# Integration_board_3008_version_2.net
KiCad netlist of a schematic drawn in EAGLE
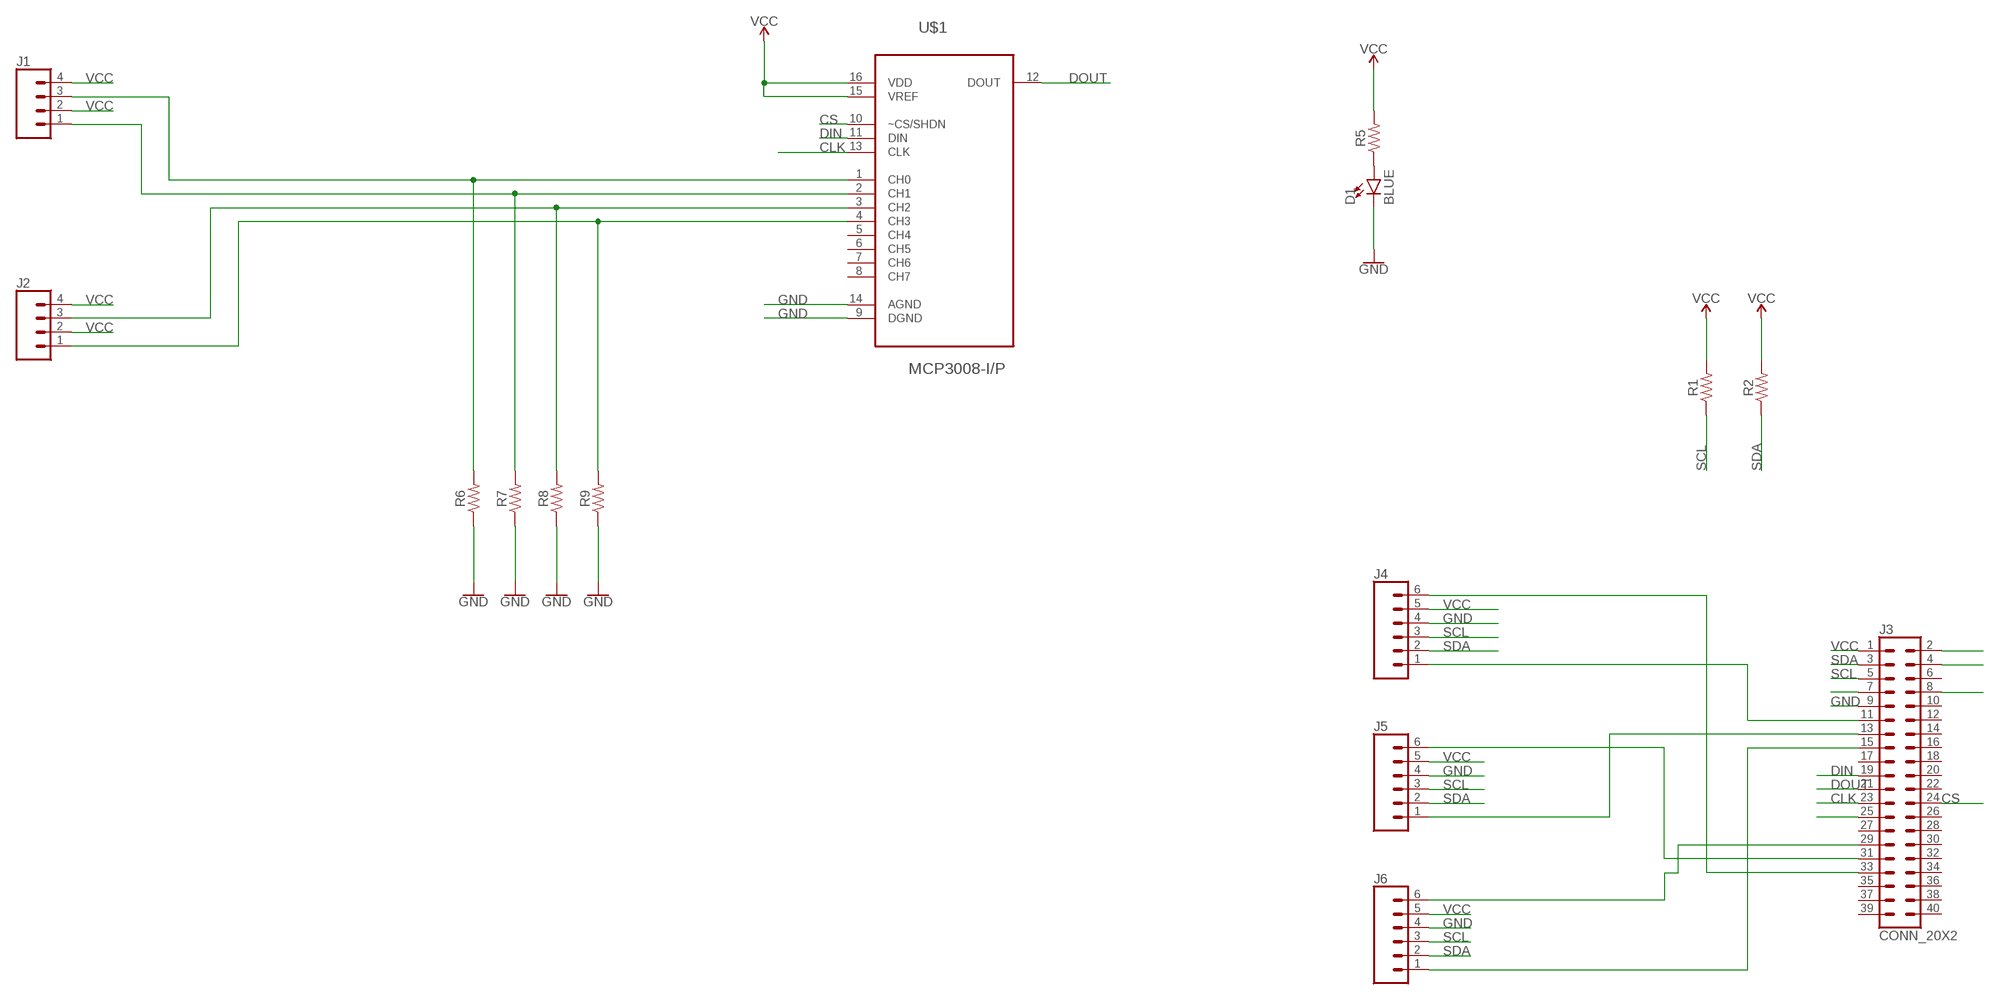
[diagram p0: schematic, sheet 1]

(export (version "E")
  (design (tool "Eeschema 10.0.6"))
  (components
    (comp (ref "D1")
      (value "BLUE")
      (footprint "eagle-import:LED-0603")
      (libsource (lib "eagle-import") (part "LED-BLUE0603"))
    )
    (comp (ref "J1")
      (value "CONN_04PTH")
      (footprint "eagle-import:1X04")
      (libsource (lib "eagle-import") (part "CONN_04PTH"))
    )
    (comp (ref "J2")
      (value "CONN_04PTH")
      (footprint "eagle-import:1X04")
      (libsource (lib "eagle-import") (part "CONN_04PTH"))
    )
    (comp (ref "J3")
      (value "CONN_20X2")
      (footprint "eagle-import:2X20")
      (libsource (lib "eagle-import") (part "CONN_20X2"))
    )
    (comp (ref "J4")
      (value "CONN_06SILK_FEMALE_PTH")
      (footprint "eagle-import:1X06")
      (libsource (lib "eagle-import") (part "CONN_06SILK_FEMALE_PTH"))
    )
    (comp (ref "J5")
      (value "CONN_06SILK_FEMALE_PTH")
      (footprint "eagle-import:1X06")
      (libsource (lib "eagle-import") (part "CONN_06SILK_FEMALE_PTH"))
    )
    (comp (ref "J6")
      (value "CONN_06SILK_FEMALE_PTH")
      (footprint "eagle-import:1X06")
      (libsource (lib "eagle-import") (part "CONN_06SILK_FEMALE_PTH"))
    )
    (comp (ref "R1")
      (value "RESISTOR0805")
      (footprint "eagle-import:0805")
      (libsource (lib "eagle-import") (part "RESISTOR0805"))
    )
    (comp (ref "R2")
      (value "RESISTOR0805")
      (footprint "eagle-import:0805")
      (libsource (lib "eagle-import") (part "RESISTOR0805"))
    )
    (comp (ref "R5")
      (value "RESISTOR0805")
      (footprint "eagle-import:0805")
      (libsource (lib "eagle-import") (part "RESISTOR0805"))
    )
    (comp (ref "R6")
      (value "RESISTOR0805")
      (footprint "eagle-import:0805")
      (libsource (lib "eagle-import") (part "RESISTOR0805"))
    )
    (comp (ref "R7")
      (value "RESISTOR0805")
      (footprint "eagle-import:0805")
      (libsource (lib "eagle-import") (part "RESISTOR0805"))
    )
    (comp (ref "R8")
      (value "RESISTOR0805")
      (footprint "eagle-import:0805")
      (libsource (lib "eagle-import") (part "RESISTOR0805"))
    )
    (comp (ref "R9")
      (value "RESISTOR0805")
      (footprint "eagle-import:0805")
      (libsource (lib "eagle-import") (part "RESISTOR0805"))
    )
    (comp (ref "U$1")
      (value "MCP3008-I/P")
      (footprint "eagle-import:DIP254P762X432-16")
      (libsource (lib "eagle-import") (part "MCP3008-I/P"))
    )
  )
  (nets
    (net (code "1") (name "/CLK") (class "Default")
      (node (ref "J3") (pin "23") (pinfunction "23_23") (pintype "passive"))
      (node (ref "U$1") (pin "13") (pinfunction "CLK_13") (pintype "input"))
    )
    (net (code "2") (name "/CS") (class "Default")
      (node (ref "J3") (pin "24") (pinfunction "24_24") (pintype "passive"))
      (node (ref "U$1") (pin "10") (pinfunction "~{CS/SHDN}_10") (pintype "input"))
    )
    (net (code "3") (name "/DIN") (class "Default")
      (node (ref "J3") (pin "19") (pinfunction "19_19") (pintype "passive"))
      (node (ref "U$1") (pin "11") (pinfunction "DIN_11") (pintype "input"))
    )
    (net (code "4") (name "/DOUT") (class "Default")
      (node (ref "J3") (pin "21") (pinfunction "21_21") (pintype "passive"))
      (node (ref "U$1") (pin "12") (pinfunction "DOUT_12") (pintype "output"))
    )
    (net (code "5") (name "/SCL") (class "Default")
      (node (ref "J3") (pin "5") (pinfunction "5_5") (pintype "passive"))
      (node (ref "J4") (pin "3") (pinfunction "3_3") (pintype "passive"))
      (node (ref "J5") (pin "3") (pinfunction "3_3") (pintype "passive"))
      (node (ref "J6") (pin "3") (pinfunction "3_3") (pintype "passive"))
      (node (ref "R1") (pin "1") (pinfunction "1_1") (pintype "passive"))
    )
    (net (code "6") (name "/SDA") (class "Default")
      (node (ref "J3") (pin "3") (pinfunction "3_3") (pintype "passive"))
      (node (ref "J4") (pin "2") (pinfunction "2_2") (pintype "passive"))
      (node (ref "J5") (pin "2") (pinfunction "2_2") (pintype "passive"))
      (node (ref "J6") (pin "2") (pinfunction "2_2") (pintype "passive"))
      (node (ref "R2") (pin "1") (pinfunction "1_1") (pintype "passive"))
    )
    (net (code "7") (name "GND") (class "Default")
      (node (ref "D1") (pin "C") (pinfunction "C_C") (pintype "passive"))
      (node (ref "J3") (pin "9") (pinfunction "9_9") (pintype "passive"))
      (node (ref "J4") (pin "4") (pinfunction "4_4") (pintype "passive"))
      (node (ref "J5") (pin "4") (pinfunction "4_4") (pintype "passive"))
      (node (ref "J6") (pin "4") (pinfunction "4_4") (pintype "passive"))
      (node (ref "R6") (pin "1") (pinfunction "1_1") (pintype "passive"))
      (node (ref "R7") (pin "1") (pinfunction "1_1") (pintype "passive"))
      (node (ref "R8") (pin "1") (pinfunction "1_1") (pintype "passive"))
      (node (ref "R9") (pin "1") (pinfunction "1_1") (pintype "passive"))
      (node (ref "U$1") (pin "14") (pinfunction "AGND_14") (pintype "passive"))
      (node (ref "U$1") (pin "9") (pinfunction "DGND_9") (pintype "passive"))
    )
    (net (code "8") (name "Net-(D1-PadA)") (class "Default")
      (node (ref "D1") (pin "A") (pinfunction "A_A") (pintype "passive"))
      (node (ref "R5") (pin "1") (pinfunction "1_1") (pintype "passive"))
    )
    (net (code "9") (name "Net-(J3-Pad11)") (class "Default")
      (node (ref "J3") (pin "11") (pinfunction "11_11") (pintype "passive"))
      (node (ref "J4") (pin "1") (pinfunction "1_1") (pintype "passive"))
    )
    (net (code "10") (name "Net-(J3-Pad13)") (class "Default")
      (node (ref "J3") (pin "13") (pinfunction "13_13") (pintype "passive"))
      (node (ref "J5") (pin "1") (pinfunction "1_1") (pintype "passive"))
    )
    (net (code "11") (name "Net-(J3-Pad15)") (class "Default")
      (node (ref "J3") (pin "15") (pinfunction "15_15") (pintype "passive"))
      (node (ref "J6") (pin "1") (pinfunction "1_1") (pintype "passive"))
    )
    (net (code "12") (name "Net-(J3-Pad29)") (class "Default")
      (node (ref "J3") (pin "29") (pinfunction "29_29") (pintype "passive"))
      (node (ref "J6") (pin "6") (pinfunction "6_6") (pintype "passive"))
    )
    (net (code "13") (name "Net-(J3-Pad31)") (class "Default")
      (node (ref "J3") (pin "31") (pinfunction "31_31") (pintype "passive"))
      (node (ref "J5") (pin "6") (pinfunction "6_6") (pintype "passive"))
    )
    (net (code "14") (name "Net-(J3-Pad33)") (class "Default")
      (node (ref "J3") (pin "33") (pinfunction "33_33") (pintype "passive"))
      (node (ref "J4") (pin "6") (pinfunction "6_6") (pintype "passive"))
    )
    (net (code "15") (name "Net-(U$1-CH0)") (class "Default")
      (node (ref "J1") (pin "3") (pinfunction "3_3") (pintype "passive"))
      (node (ref "R6") (pin "2") (pinfunction "2_2") (pintype "passive"))
      (node (ref "U$1") (pin "1") (pinfunction "CH0_1") (pintype "input"))
    )
    (net (code "16") (name "Net-(U$1-CH1)") (class "Default")
      (node (ref "J1") (pin "1") (pinfunction "1_1") (pintype "passive"))
      (node (ref "R7") (pin "2") (pinfunction "2_2") (pintype "passive"))
      (node (ref "U$1") (pin "2") (pinfunction "CH1_2") (pintype "input"))
    )
    (net (code "17") (name "Net-(U$1-CH2)") (class "Default")
      (node (ref "J2") (pin "3") (pinfunction "3_3") (pintype "passive"))
      (node (ref "R8") (pin "2") (pinfunction "2_2") (pintype "passive"))
      (node (ref "U$1") (pin "3") (pinfunction "CH2_3") (pintype "input"))
    )
    (net (code "18") (name "Net-(U$1-CH3)") (class "Default")
      (node (ref "J2") (pin "1") (pinfunction "1_1") (pintype "passive"))
      (node (ref "R9") (pin "2") (pinfunction "2_2") (pintype "passive"))
      (node (ref "U$1") (pin "4") (pinfunction "CH3_4") (pintype "input"))
    )
    (net (code "19") (name "VCC") (class "Default")
      (node (ref "J1") (pin "2") (pinfunction "2_2") (pintype "passive"))
      (node (ref "J1") (pin "4") (pinfunction "4_4") (pintype "passive"))
      (node (ref "J2") (pin "2") (pinfunction "2_2") (pintype "passive"))
      (node (ref "J2") (pin "4") (pinfunction "4_4") (pintype "passive"))
      (node (ref "J3") (pin "1") (pinfunction "1_1") (pintype "passive"))
      (node (ref "J4") (pin "5") (pinfunction "5_5") (pintype "passive"))
      (node (ref "J5") (pin "5") (pinfunction "5_5") (pintype "passive"))
      (node (ref "J6") (pin "5") (pinfunction "5_5") (pintype "passive"))
      (node (ref "R1") (pin "2") (pinfunction "2_2") (pintype "passive"))
      (node (ref "R2") (pin "2") (pinfunction "2_2") (pintype "passive"))
      (node (ref "R5") (pin "2") (pinfunction "2_2") (pintype "passive"))
      (node (ref "U$1") (pin "15") (pinfunction "VREF_15") (pintype "power_in"))
      (node (ref "U$1") (pin "16") (pinfunction "VDD_16") (pintype "power_in"))
    )
    (net (code "20") (name "unconnected-(J3-Pad2)") (class "Default")
      (node (ref "J3") (pin "2") (pinfunction "2_2") (pintype "passive"))
    )
    (net (code "21") (name "unconnected-(J3-Pad4)") (class "Default")
      (node (ref "J3") (pin "4") (pinfunction "4_4") (pintype "passive"))
    )
    (net (code "22") (name "unconnected-(J3-Pad6)") (class "Default")
      (node (ref "J3") (pin "6") (pinfunction "6_6") (pintype "passive"))
    )
    (net (code "23") (name "unconnected-(J3-Pad7)") (class "Default")
      (node (ref "J3") (pin "7") (pinfunction "7_7") (pintype "passive"))
    )
    (net (code "24") (name "unconnected-(J3-Pad8)") (class "Default")
      (node (ref "J3") (pin "8") (pinfunction "8_8") (pintype "passive"))
    )
    (net (code "25") (name "unconnected-(J3-Pad10)") (class "Default")
      (node (ref "J3") (pin "10") (pinfunction "10_10") (pintype "passive"))
    )
    (net (code "26") (name "unconnected-(J3-Pad12)") (class "Default")
      (node (ref "J3") (pin "12") (pinfunction "12_12") (pintype "passive"))
    )
    (net (code "27") (name "unconnected-(J3-Pad14)") (class "Default")
      (node (ref "J3") (pin "14") (pinfunction "14_14") (pintype "passive"))
    )
    (net (code "28") (name "unconnected-(J3-Pad16)") (class "Default")
      (node (ref "J3") (pin "16") (pinfunction "16_16") (pintype "passive"))
    )
    (net (code "29") (name "unconnected-(J3-Pad17)") (class "Default")
      (node (ref "J3") (pin "17") (pinfunction "17_17") (pintype "passive"))
    )
    (net (code "30") (name "unconnected-(J3-Pad18)") (class "Default")
      (node (ref "J3") (pin "18") (pinfunction "18_18") (pintype "passive"))
    )
    (net (code "31") (name "unconnected-(J3-Pad20)") (class "Default")
      (node (ref "J3") (pin "20") (pinfunction "20_20") (pintype "passive"))
    )
    (net (code "32") (name "unconnected-(J3-Pad22)") (class "Default")
      (node (ref "J3") (pin "22") (pinfunction "22_22") (pintype "passive"))
    )
    (net (code "33") (name "unconnected-(J3-Pad25)") (class "Default")
      (node (ref "J3") (pin "25") (pinfunction "25_25") (pintype "passive"))
    )
    (net (code "34") (name "unconnected-(J3-Pad26)") (class "Default")
      (node (ref "J3") (pin "26") (pinfunction "26_26") (pintype "passive"))
    )
    (net (code "35") (name "unconnected-(J3-Pad27)") (class "Default")
      (node (ref "J3") (pin "27") (pinfunction "27_27") (pintype "passive"))
    )
    (net (code "36") (name "unconnected-(J3-Pad28)") (class "Default")
      (node (ref "J3") (pin "28") (pinfunction "28_28") (pintype "passive"))
    )
    (net (code "37") (name "unconnected-(J3-Pad30)") (class "Default")
      (node (ref "J3") (pin "30") (pinfunction "30_30") (pintype "passive"))
    )
    (net (code "38") (name "unconnected-(J3-Pad32)") (class "Default")
      (node (ref "J3") (pin "32") (pinfunction "32_32") (pintype "passive"))
    )
    (net (code "39") (name "unconnected-(J3-Pad34)") (class "Default")
      (node (ref "J3") (pin "34") (pinfunction "34_34") (pintype "passive"))
    )
    (net (code "40") (name "unconnected-(J3-Pad35)") (class "Default")
      (node (ref "J3") (pin "35") (pinfunction "35_35") (pintype "passive"))
    )
    (net (code "41") (name "unconnected-(J3-Pad36)") (class "Default")
      (node (ref "J3") (pin "36") (pinfunction "36_36") (pintype "passive"))
    )
    (net (code "42") (name "unconnected-(J3-Pad37)") (class "Default")
      (node (ref "J3") (pin "37") (pinfunction "37_37") (pintype "passive"))
    )
    (net (code "43") (name "unconnected-(J3-Pad38)") (class "Default")
      (node (ref "J3") (pin "38") (pinfunction "38_38") (pintype "passive"))
    )
    (net (code "44") (name "unconnected-(J3-Pad39)") (class "Default")
      (node (ref "J3") (pin "39") (pinfunction "39_39") (pintype "passive"))
    )
    (net (code "45") (name "unconnected-(J3-Pad40)") (class "Default")
      (node (ref "J3") (pin "40") (pinfunction "40_40") (pintype "passive"))
    )
    (net (code "46") (name "unconnected-(U$1-CH4-Pad5)") (class "Default")
      (node (ref "U$1") (pin "5") (pinfunction "CH4_5") (pintype "input"))
    )
    (net (code "47") (name "unconnected-(U$1-CH5-Pad6)") (class "Default")
      (node (ref "U$1") (pin "6") (pinfunction "CH5_6") (pintype "input"))
    )
    (net (code "48") (name "unconnected-(U$1-CH6-Pad7)") (class "Default")
      (node (ref "U$1") (pin "7") (pinfunction "CH6_7") (pintype "input"))
    )
    (net (code "49") (name "unconnected-(U$1-CH7-Pad8)") (class "Default")
      (node (ref "U$1") (pin "8") (pinfunction "CH7_8") (pintype "input"))
    )
  )
)
